# ET-COM.net
KiCad netlist of a schematic drawn in Altium Designer
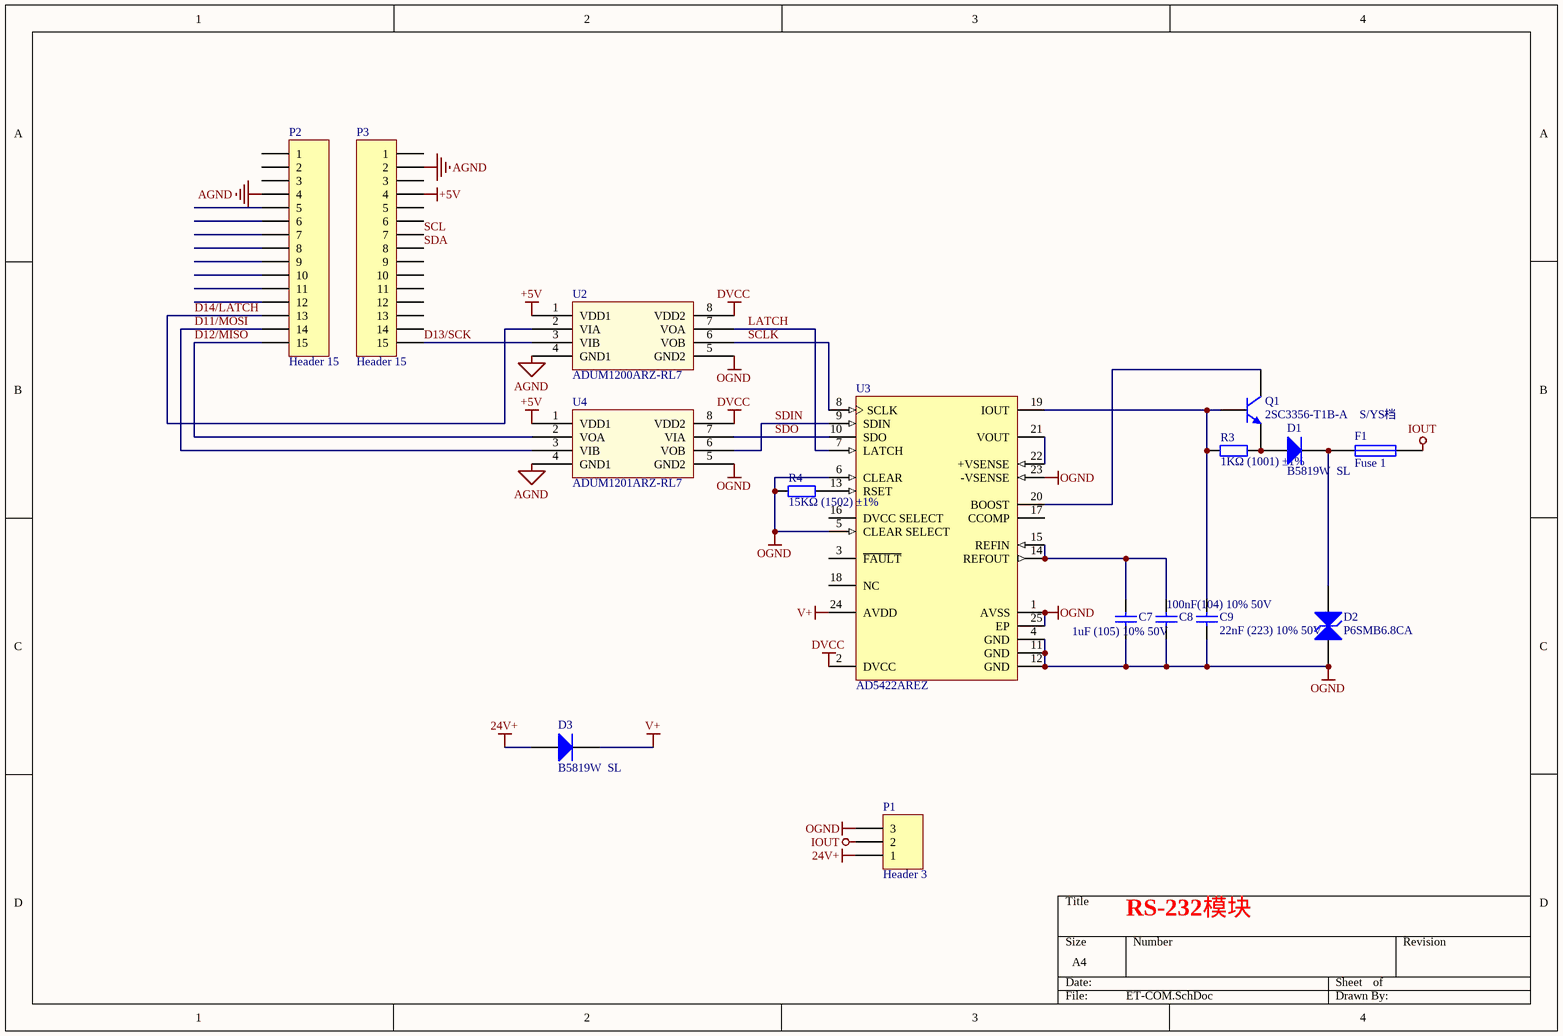
[diagram p0: ET-COM.SchDoc]

(export (version "E")
  (design (tool "Eeschema 10.0.6"))
  (components
    (comp (ref "C7")
      (value "1uF (105) 10% 50V")
      (footprint "LC-0805_C")
      (description "贴片电容")
      (libsource (lib "Miscellaneous Devices LC") (part "0805 1uF (105) 10% 50V"))
    )
    (comp (ref "C8")
      (value "100nF(104) 10% 50V")
      (footprint "LC-0805_C")
      (description "贴片电容")
      (libsource (lib "Miscellaneous Devices LC") (part "0805 100nF(104) 10% 50V"))
    )
    (comp (ref "C9")
      (value "22nF (223) 10% 50V")
      (footprint "LC-0805_C")
      (description "贴片电容")
      (libsource (lib "Miscellaneous Devices LC") (part "0805 22nF (223) 10% 50V"))
    )
    (comp (ref "D1")
      (value "B5819W  SL")
      (footprint "LC-SOD-123")
      (description "肖特基二极管")
      (libsource (lib "Miscellaneous Devices LC") (part "SOD-123 B5819W  SL"))
    )
    (comp (ref "D2")
      (value "P6SMB6.8CA")
      (footprint "LC-SMB(DO-214AA)_S1")
      (description "TVS")
      (libsource (lib "Miscellaneous Devices LC") (part "SMB/DO-214AA P6SMB6.8CA"))
    )
    (comp (ref "D3")
      (value "B5819W  SL")
      (footprint "SOD-123")
      (description "肖特基二极管")
      (libsource (lib "Miscellaneous Devices LC") (part "SOD-123 B5819W  SL"))
    )
    (comp (ref "F1")
      (value "Fuse 1")
      (footprint "LC-1206_L")
      (description "Fuse")
      (fields (field (name "PUBLISHER") "Altium Limited"))
      (libsource (lib "Miscellaneous Devices") (part "Fuse 1"))
    )
    (comp (ref "P1")
      (value "Header 3")
      (footprint "connector_x3")
      (description "Header, 3-Pin")
      (fields (field (name "PUBLISHER") "Altium Limited"))
      (libsource (lib "Miscellaneous Connectors") (part "Header 3"))
    )
    (comp (ref "P2")
      (value "Header 15")
      (footprint "HDR1X15")
      (description "Header, 15-Pin")
      (fields (field (name "PUBLISHER") "Altium Limited"))
      (libsource (lib "Miscellaneous Connectors") (part "Header 15"))
    )
    (comp (ref "P3")
      (value "Header 15")
      (footprint "HDR1X15")
      (description "Header, 15-Pin")
      (fields (field (name "PUBLISHER") "Altium Limited"))
      (libsource (lib "") (part "Header 15_1"))
    )
    (comp (ref "Q1")
      (value "2SC3356-T1B-A    S/YS档")
      (footprint "LC-SOT-23(SOT-23-3)")
      (description "三极管")
      (libsource (lib "Miscellaneous Devices LC") (part "SOT-23 2SC3356-T1B-A    S/YS档"))
    )
    (comp (ref "R3")
      (value "1KΩ (1001) ±1%")
      (footprint "LC-0805_R")
      (description "贴片电阻")
      (libsource (lib "Miscellaneous Devices LC") (part "0805 1KΩ (1001) 1%"))
    )
    (comp (ref "R4")
      (value "15KΩ (1502) ±1%")
      (footprint "LC-0805_R")
      (description "贴片电阻")
      (libsource (lib "Miscellaneous Devices LC") (part "0805 15KΩ (1502) 1%"))
    )
    (comp (ref "U2")
      (value "ADUM1200ARZ-RL7")
      (footprint "LC-SOIC-8_150mil")
      (description "隔离器")
      (libsource (lib "Miscellaneous Devices LC") (part "ADUM1201ARZ-RL7"))
    )
    (comp (ref "U3")
      (value "AD5422AREZ")
      (footprint "RE-24_N")
      (fields (field (name "GENERIC PART NUMBER") "AD5422") (field (name "MANUFACTURER") "Analog Devices"))
      (libsource (lib "AD Data Converters Digital-to-Analog Converters") (part "AD5422AREZ"))
    )
    (comp (ref "U4")
      (value "ADUM1201ARZ-RL7")
      (footprint "LC-SOIC-8_150mil")
      (description "隔离器")
      (libsource (lib "Miscellaneous Devices LC") (part "ADUM1201ARZ-RL7"))
    )
  )
  (nets
    (net (code "1") (name "+5V") (class "Default")
      (node (ref "P3") (pin "4") (pinfunction "4_4") (pintype "passive"))
      (node (ref "U2") (pin "1") (pinfunction "VDD1_1") (pintype "passive"))
      (node (ref "U4") (pin "1") (pinfunction "VDD1_1") (pintype "passive"))
    )
    (net (code "2") (name "/D11{slash}MOSI") (class "Default")
      (node (ref "P2") (pin "14") (pinfunction "14_14") (pintype "passive"))
      (node (ref "U4") (pin "3") (pinfunction "VIB_3") (pintype "passive"))
    )
    (net (code "3") (name "/D12{slash}MISO") (class "Default")
      (node (ref "P2") (pin "15") (pinfunction "15_15") (pintype "passive"))
      (node (ref "U4") (pin "2") (pinfunction "VIA_2") (pintype "passive"))
    )
    (net (code "4") (name "/D13{slash}SCK") (class "Default")
      (node (ref "P3") (pin "15") (pinfunction "15_15") (pintype "passive"))
      (node (ref "U2") (pin "3") (pinfunction "VIB_3") (pintype "passive"))
    )
    (net (code "5") (name "/D14{slash}LATCH") (class "Default")
      (node (ref "P2") (pin "13") (pinfunction "13_13") (pintype "passive"))
      (node (ref "U2") (pin "2") (pinfunction "VIA_2") (pintype "passive"))
    )
    (net (code "6") (name "/LATCH") (class "Default")
      (node (ref "U2") (pin "7") (pinfunction "VOA_7") (pintype "passive"))
      (node (ref "U3") (pin "7") (pinfunction "LATCH_7") (pintype "input"))
    )
    (net (code "7") (name "/SCL") (class "Default")
      (node (ref "P3") (pin "7") (pinfunction "7_7") (pintype "passive"))
    )
    (net (code "8") (name "/SCLK") (class "Default")
      (node (ref "U2") (pin "6") (pinfunction "VOB_6") (pintype "passive"))
      (node (ref "U3") (pin "8") (pinfunction "SCLK_8") (pintype "input"))
    )
    (net (code "9") (name "/SDA") (class "Default")
      (node (ref "P3") (pin "8") (pinfunction "8_8") (pintype "passive"))
    )
    (net (code "10") (name "/SDIN") (class "Default")
      (node (ref "U3") (pin "9") (pinfunction "SDIN_9") (pintype "input"))
      (node (ref "U4") (pin "6") (pinfunction "VOB_6") (pintype "passive"))
    )
    (net (code "11") (name "/SDO") (class "Default")
      (node (ref "U3") (pin "10") (pinfunction "SDO_10") (pintype "tri_state"))
      (node (ref "U4") (pin "7") (pinfunction "VOA_7") (pintype "passive"))
    )
    (net (code "12") (name "24V+") (class "Default")
      (node (ref "D3") (pin "1") (pinfunction "A_1") (pintype "passive"))
      (node (ref "P1") (pin "1") (pinfunction "1_1") (pintype "passive"))
    )
    (net (code "13") (name "AGND") (class "Default")
      (node (ref "P2") (pin "4") (pinfunction "4_4") (pintype "passive"))
      (node (ref "P3") (pin "2") (pinfunction "2_2") (pintype "passive"))
      (node (ref "U2") (pin "4") (pinfunction "GND1_4") (pintype "passive"))
      (node (ref "U4") (pin "4") (pinfunction "GND1_4") (pintype "passive"))
    )
    (net (code "14") (name "DVCC") (class "Default")
      (node (ref "U2") (pin "8") (pinfunction "VDD2_8") (pintype "passive"))
      (node (ref "U3") (pin "2") (pinfunction "DVCC_2") (pintype "power_in"))
      (node (ref "U4") (pin "8") (pinfunction "VDD2_8") (pintype "passive"))
    )
    (net (code "15") (name "IOUT") (class "Default")
      (node (ref "F1") (pin "2") (pinfunction "2_2") (pintype "passive"))
      (node (ref "P1") (pin "2") (pinfunction "2_2") (pintype "passive"))
    )
    (net (code "16") (name "Net-(D1-A)") (class "Default")
      (node (ref "D1") (pin "1") (pinfunction "A_1") (pintype "passive"))
      (node (ref "Q1") (pin "2") (pinfunction "E_2") (pintype "passive"))
      (node (ref "R3") (pin "2") (pinfunction "2_2") (pintype "passive"))
    )
    (net (code "17") (name "Net-(D1-K)") (class "Default")
      (node (ref "D1") (pin "2") (pinfunction "K_2") (pintype "passive"))
      (node (ref "D2") (pin "2") (pinfunction "K_2") (pintype "passive"))
      (node (ref "F1") (pin "1") (pinfunction "1_1") (pintype "passive"))
    )
    (net (code "18") (name "Net-(Q1-B)") (class "Default")
      (node (ref "C9") (pin "2") (pinfunction "2_2") (pintype "passive"))
      (node (ref "Q1") (pin "1") (pinfunction "B_1") (pintype "passive"))
      (node (ref "R3") (pin "1") (pinfunction "1_1") (pintype "passive"))
      (node (ref "U3") (pin "19") (pinfunction "IOUT_19") (pintype "tri_state"))
    )
    (net (code "19") (name "Net-(Q1-C)") (class "Default")
      (node (ref "Q1") (pin "3") (pinfunction "C_3") (pintype "passive"))
      (node (ref "U3") (pin "20") (pinfunction "BOOST_20") (pintype "passive"))
    )
    (net (code "20") (name "Net-(U3-+VSENSE)") (class "Default")
      (node (ref "U3") (pin "21") (pinfunction "VOUT_21") (pintype "tri_state"))
      (node (ref "U3") (pin "22") (pinfunction "+VSENSE_22") (pintype "input"))
    )
    (net (code "21") (name "Net-(U3-REFIN)") (class "Default")
      (node (ref "C7") (pin "2") (pinfunction "2_2") (pintype "passive"))
      (node (ref "C8") (pin "2") (pinfunction "2_2") (pintype "passive"))
      (node (ref "U3") (pin "14") (pinfunction "REFOUT_14") (pintype "output"))
      (node (ref "U3") (pin "15") (pinfunction "REFIN_15") (pintype "input"))
    )
    (net (code "22") (name "Net-(U3-RSET)") (class "Default")
      (node (ref "R4") (pin "2") (pinfunction "2_2") (pintype "passive"))
      (node (ref "U3") (pin "13") (pinfunction "RSET_13") (pintype "input"))
    )
    (net (code "23") (name "OGND") (class "Default")
      (node (ref "C7") (pin "1") (pinfunction "1_1") (pintype "passive"))
      (node (ref "C8") (pin "1") (pinfunction "1_1") (pintype "passive"))
      (node (ref "C9") (pin "1") (pinfunction "1_1") (pintype "passive"))
      (node (ref "D2") (pin "1") (pinfunction "A_1") (pintype "passive"))
      (node (ref "P1") (pin "3") (pinfunction "3_3") (pintype "passive"))
      (node (ref "R4") (pin "1") (pinfunction "1_1") (pintype "passive"))
      (node (ref "U2") (pin "5") (pinfunction "GND2_5") (pintype "passive"))
      (node (ref "U3") (pin "1") (pinfunction "AVSS_1") (pintype "power_in"))
      (node (ref "U3") (pin "11") (pinfunction "GND_11") (pintype "power_in"))
      (node (ref "U3") (pin "12") (pinfunction "GND_12") (pintype "power_in"))
      (node (ref "U3") (pin "23") (pinfunction "-VSENSE_23") (pintype "input"))
      (node (ref "U3") (pin "25") (pinfunction "EP_25") (pintype "passive"))
      (node (ref "U3") (pin "4") (pinfunction "GND_4") (pintype "power_in"))
      (node (ref "U3") (pin "5") (pinfunction "CLEAR_SELECT_5") (pintype "input"))
      (node (ref "U3") (pin "6") (pinfunction "CLEAR_6") (pintype "input"))
      (node (ref "U4") (pin "5") (pinfunction "GND2_5") (pintype "passive"))
    )
    (net (code "24") (name "V+") (class "Default")
      (node (ref "D3") (pin "2") (pinfunction "K_2") (pintype "passive"))
      (node (ref "U3") (pin "24") (pinfunction "AVDD_24") (pintype "power_in"))
    )
    (net (code "25") (name "unconnected-(P2-Pad1)") (class "Default")
      (node (ref "P2") (pin "1") (pinfunction "1_1") (pintype "passive"))
    )
    (net (code "26") (name "unconnected-(P2-Pad2)") (class "Default")
      (node (ref "P2") (pin "2") (pinfunction "2_2") (pintype "passive"))
    )
    (net (code "27") (name "unconnected-(P2-Pad3)") (class "Default")
      (node (ref "P2") (pin "3") (pinfunction "3_3") (pintype "passive"))
    )
    (net (code "28") (name "unconnected-(P2-Pad5)") (class "Default")
      (node (ref "P2") (pin "5") (pinfunction "5_5") (pintype "passive"))
    )
    (net (code "29") (name "unconnected-(P2-Pad6)") (class "Default")
      (node (ref "P2") (pin "6") (pinfunction "6_6") (pintype "passive"))
    )
    (net (code "30") (name "unconnected-(P2-Pad7)") (class "Default")
      (node (ref "P2") (pin "7") (pinfunction "7_7") (pintype "passive"))
    )
    (net (code "31") (name "unconnected-(P2-Pad8)") (class "Default")
      (node (ref "P2") (pin "8") (pinfunction "8_8") (pintype "passive"))
    )
    (net (code "32") (name "unconnected-(P2-Pad9)") (class "Default")
      (node (ref "P2") (pin "9") (pinfunction "9_9") (pintype "passive"))
    )
    (net (code "33") (name "unconnected-(P2-Pad10)") (class "Default")
      (node (ref "P2") (pin "10") (pinfunction "10_10") (pintype "passive"))
    )
    (net (code "34") (name "unconnected-(P2-Pad11)") (class "Default")
      (node (ref "P2") (pin "11") (pinfunction "11_11") (pintype "passive"))
    )
    (net (code "35") (name "unconnected-(P2-Pad12)") (class "Default")
      (node (ref "P2") (pin "12") (pinfunction "12_12") (pintype "passive"))
    )
    (net (code "36") (name "unconnected-(P3-Pad1)") (class "Default")
      (node (ref "P3") (pin "1") (pinfunction "1_1") (pintype "passive"))
    )
    (net (code "37") (name "unconnected-(P3-Pad3)") (class "Default")
      (node (ref "P3") (pin "3") (pinfunction "3_3") (pintype "passive"))
    )
    (net (code "38") (name "unconnected-(P3-Pad5)") (class "Default")
      (node (ref "P3") (pin "5") (pinfunction "5_5") (pintype "passive"))
    )
    (net (code "39") (name "unconnected-(P3-Pad6)") (class "Default")
      (node (ref "P3") (pin "6") (pinfunction "6_6") (pintype "passive"))
    )
    (net (code "40") (name "unconnected-(P3-Pad9)") (class "Default")
      (node (ref "P3") (pin "9") (pinfunction "9_9") (pintype "passive"))
    )
    (net (code "41") (name "unconnected-(P3-Pad10)") (class "Default")
      (node (ref "P3") (pin "10") (pinfunction "10_10") (pintype "passive"))
    )
    (net (code "42") (name "unconnected-(P3-Pad11)") (class "Default")
      (node (ref "P3") (pin "11") (pinfunction "11_11") (pintype "passive"))
    )
    (net (code "43") (name "unconnected-(P3-Pad12)") (class "Default")
      (node (ref "P3") (pin "12") (pinfunction "12_12") (pintype "passive"))
    )
    (net (code "44") (name "unconnected-(P3-Pad13)") (class "Default")
      (node (ref "P3") (pin "13") (pinfunction "13_13") (pintype "passive"))
    )
    (net (code "45") (name "unconnected-(P3-Pad14)") (class "Default")
      (node (ref "P3") (pin "14") (pinfunction "14_14") (pintype "passive"))
    )
    (net (code "46") (name "unconnected-(U3-CCOMP-Pad17)") (class "Default")
      (node (ref "U3") (pin "17") (pinfunction "CCOMP_17") (pintype "passive"))
    )
    (net (code "47") (name "unconnected-(U3-DVCC_SELECT-Pad16)") (class "Default")
      (node (ref "U3") (pin "16") (pinfunction "DVCC_SELECT_16") (pintype "passive"))
    )
    (net (code "48") (name "unconnected-(U3-NC-Pad18)") (class "Default")
      (node (ref "U3") (pin "18") (pinfunction "NC_18") (pintype "passive"))
    )
    (net (code "49") (name "unconnected-(U3-~{FAULT}-Pad3)") (class "Default")
      (node (ref "U3") (pin "3") (pinfunction "~{FAULT}_3") (pintype "open_collector"))
    )
  )
)
